# SmartSocket_v3.net
KiCad netlist of a schematic drawn in Altium Designer
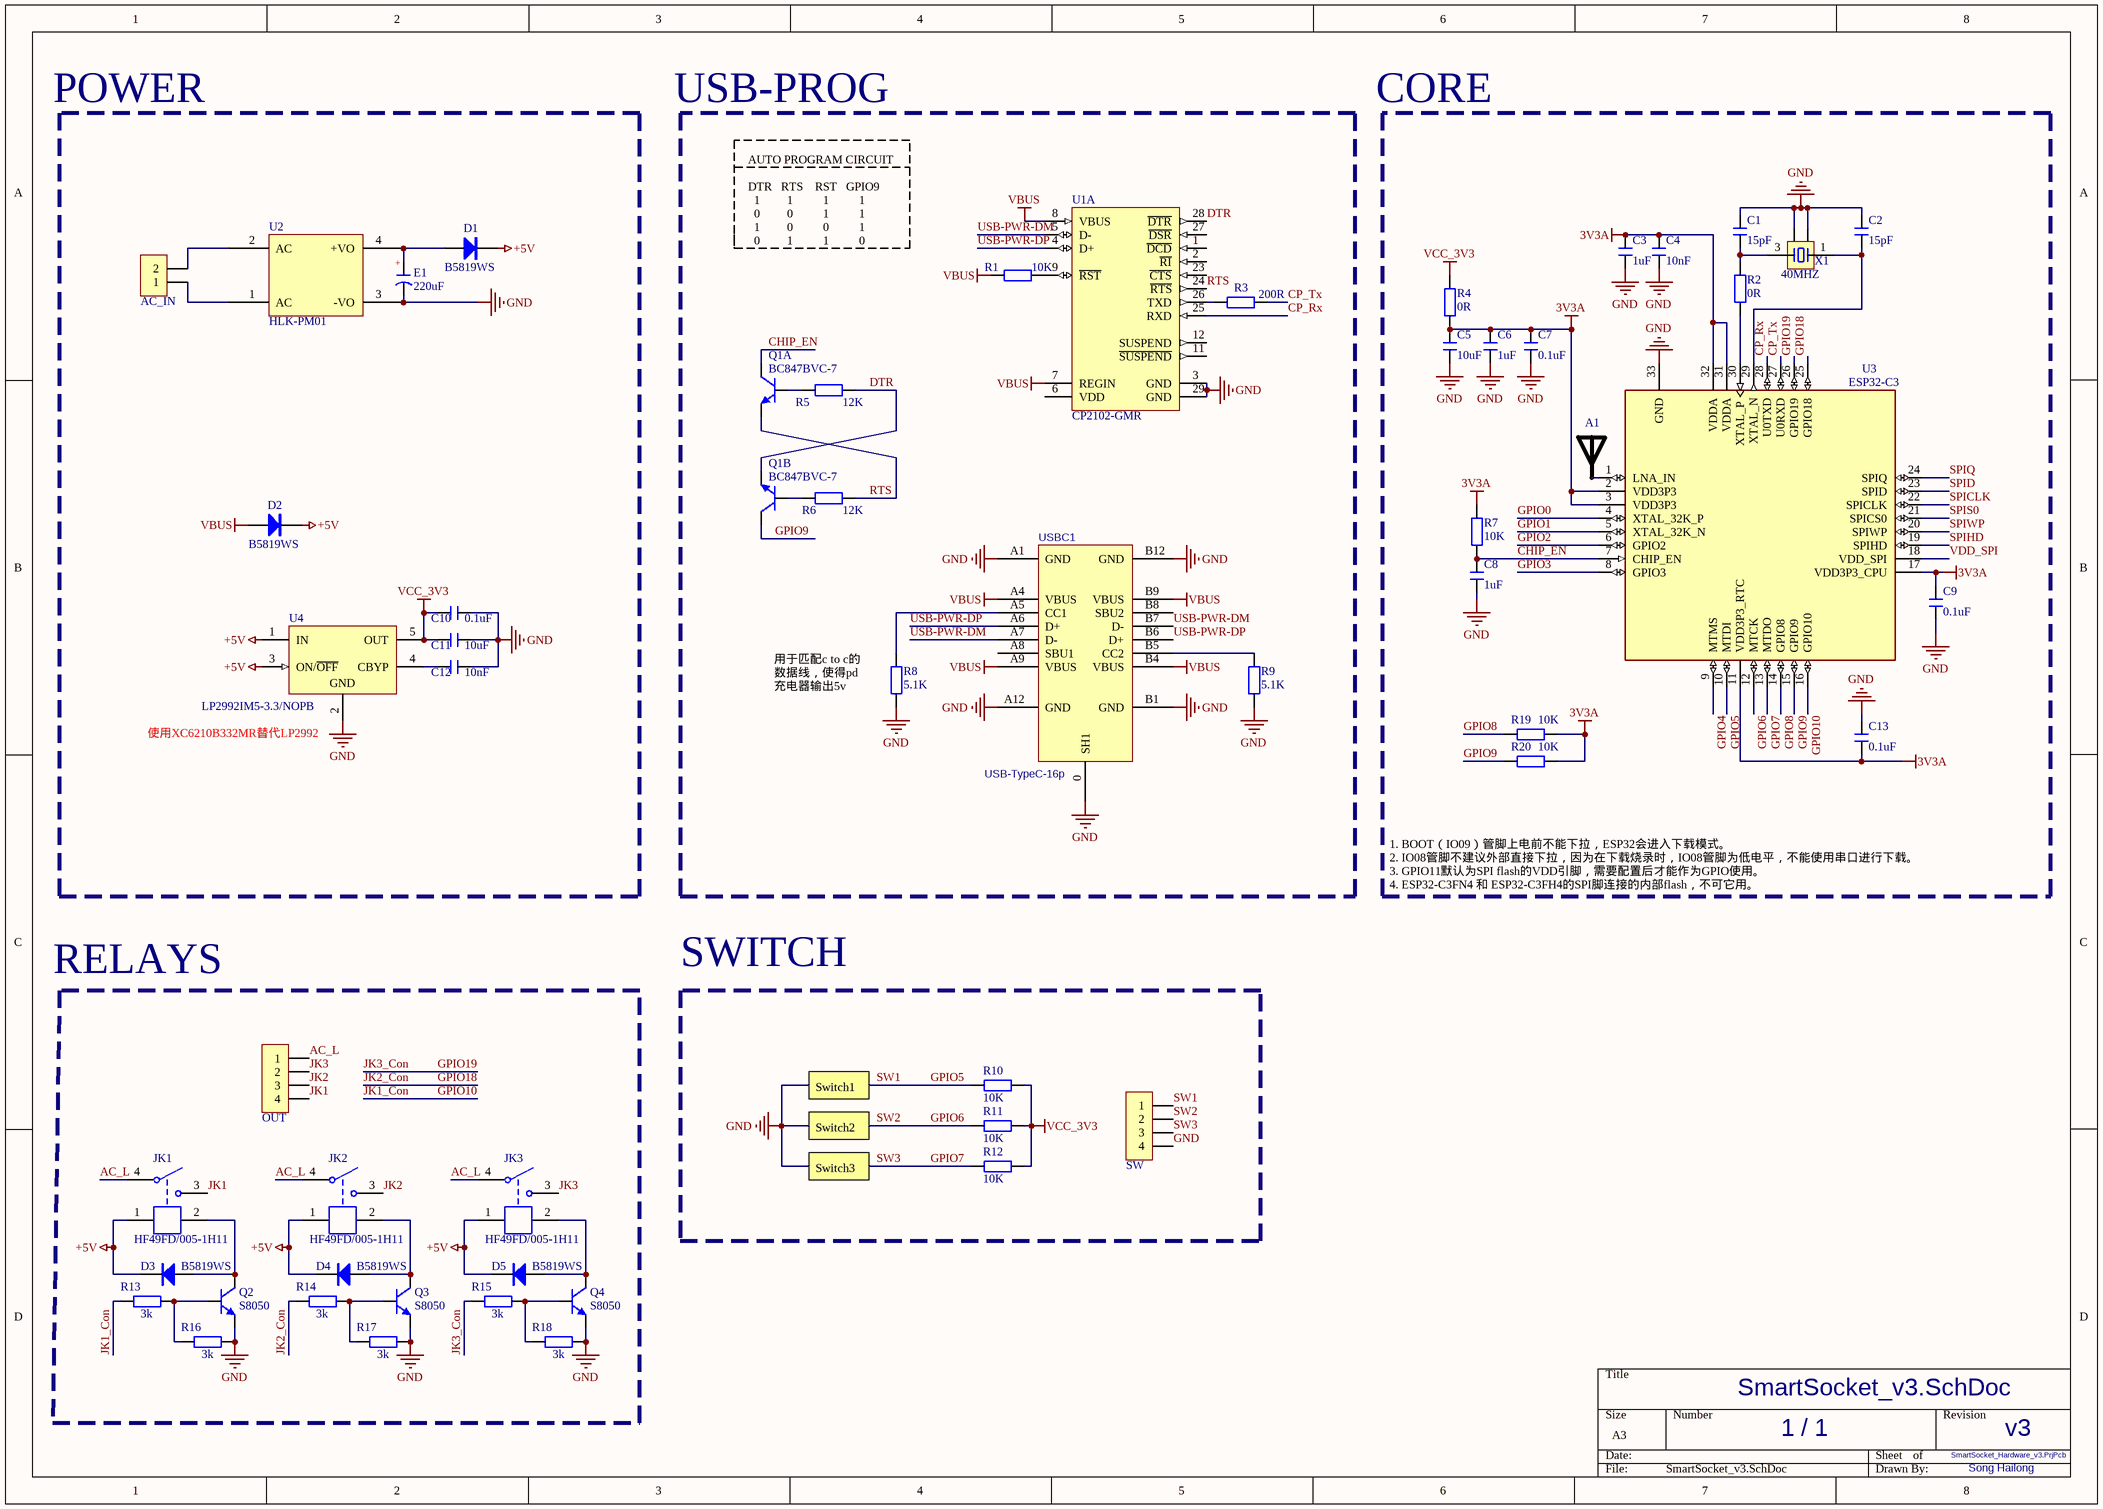
[diagram p0: SmartSocket_v3.SchDoc]

(export (version "E")
  (design (tool "Eeschema 10.0.6"))
  (components
    (comp (ref "A1")
      (value "AN2051-245")
      (footprint "AN2051-245")
      (description "天线AN2051-245")
      (libsource (lib "U8Library") (part "ANT-Rainsun-AP2051"))
    )
    (comp (ref "AC_IN")
      (value "HDR-1X2")
      (footprint "KF301-5.0-2P")
      (description "2P接插件")
      (fields (field (name "版权归属") "源创客"))
      (libsource (lib "U8Library") (part "Header 02 5.0"))
    )
    (comp (ref "C1")
      (value "15pF")
      (footprint "C 0402_L")
      (description "无极性贴片电容")
      (fields (field (name "版权归属") "源创客"))
      (libsource (lib "U8Library") (part "C"))
    )
    (comp (ref "C2")
      (value "15pF")
      (footprint "C 0402_L")
      (description "无极性贴片电容")
      (fields (field (name "版权归属") "源创客"))
      (libsource (lib "U8Library") (part "C"))
    )
    (comp (ref "C3")
      (value "1uF")
      (footprint "C 0402_L")
      (description "无极性贴片电容")
      (fields (field (name "版权归属") "源创客"))
      (libsource (lib "U8Library") (part "C"))
    )
    (comp (ref "C4")
      (value "10nF")
      (footprint "C 0402_L")
      (description "无极性贴片电容")
      (fields (field (name "版权归属") "源创客"))
      (libsource (lib "U8Library") (part "C"))
    )
    (comp (ref "C5")
      (value "10uF")
      (footprint "C 0402_L")
      (description "无极性贴片电容")
      (fields (field (name "版权归属") "源创客"))
      (libsource (lib "U8Library") (part "C"))
    )
    (comp (ref "C6")
      (value "1uF")
      (footprint "C 0402_L")
      (description "无极性贴片电容")
      (fields (field (name "版权归属") "源创客"))
      (libsource (lib "U8Library") (part "C"))
    )
    (comp (ref "C7")
      (value "0.1uF")
      (footprint "C 0402_L")
      (description "无极性贴片电容")
      (fields (field (name "版权归属") "源创客"))
      (libsource (lib "U8Library") (part "C"))
    )
    (comp (ref "C8")
      (value "1uF")
      (footprint "C 0402_L")
      (description "无极性贴片电容")
      (fields (field (name "版权归属") "源创客"))
      (libsource (lib "U8Library") (part "C"))
    )
    (comp (ref "C9")
      (value "0.1uF")
      (footprint "C 0402_L")
      (description "无极性贴片电容")
      (fields (field (name "版权归属") "源创客"))
      (libsource (lib "U8Library") (part "C"))
    )
    (comp (ref "C10")
      (value "0.1uF")
      (footprint "C 0402_L")
      (description "无极性贴片电容")
      (fields (field (name "版权归属") "源创客"))
      (libsource (lib "U8Library") (part "C"))
    )
    (comp (ref "C11")
      (value "10uF")
      (footprint "C 0402_L")
      (description "无极性贴片电容")
      (fields (field (name "版权归属") "源创客"))
      (libsource (lib "U8Library") (part "C"))
    )
    (comp (ref "C12")
      (value "10nF")
      (footprint "C 0402_L")
      (description "无极性贴片电容")
      (fields (field (name "版权归属") "源创客"))
      (libsource (lib "U8Library") (part "C"))
    )
    (comp (ref "C13")
      (value "0.1uF")
      (footprint "C 0402_L")
      (description "无极性贴片电容")
      (fields (field (name "版权归属") "源创客"))
      (libsource (lib "U8Library") (part "C"))
    )
    (comp (ref "D1")
      (value "B5819WS")
      (footprint "SOD-323")
      (description "肖特基二极管")
      (fields (field (name "版权归属") "源创客"))
      (libsource (lib "U8Library") (part "1N5819"))
    )
    (comp (ref "D2")
      (value "B5819WS")
      (footprint "SOD-323")
      (description "肖特基二极管")
      (fields (field (name "版权归属") "源创客"))
      (libsource (lib "U8Library") (part "1N5819"))
    )
    (comp (ref "D3")
      (value "B5819WS")
      (footprint "SOD-323")
      (description "肖特基二极管")
      (fields (field (name "版权归属") "源创客"))
      (libsource (lib "U8Library") (part "1N5819"))
    )
    (comp (ref "D4")
      (value "B5819WS")
      (footprint "SOD-323")
      (description "肖特基二极管")
      (fields (field (name "版权归属") "源创客"))
      (libsource (lib "U8Library") (part "1N5819"))
    )
    (comp (ref "D5")
      (value "B5819WS")
      (footprint "SOD-323")
      (description "肖特基二极管")
      (fields (field (name "版权归属") "源创客"))
      (libsource (lib "U8Library") (part "1N5819"))
    )
    (comp (ref "E1")
      (value "220uF")
      (footprint "CD D(7343)")
      (description "贴片钽电容")
      (fields (field (name "版权归属") "源创客"))
      (libsource (lib "U8Library") (part "C-CD"))
    )
    (comp (ref "JK1")
      (value "HF49FD/005-1H11")
      (footprint "HF49-XX-1H11")
      (description "5V一组常开")
      (libsource (lib "U8Library") (part "HF49FD/005-1H11"))
    )
    (comp (ref "JK2")
      (value "HF49FD/005-1H11")
      (footprint "HF49-XX-1H11")
      (description "5V一组常开")
      (libsource (lib "U8Library") (part "HF49FD/005-1H11"))
    )
    (comp (ref "JK3")
      (value "HF49FD/005-1H11")
      (footprint "HF49-XX-1H11")
      (description "5V一组常开")
      (libsource (lib "U8Library") (part "HF49FD/005-1H11"))
    )
    (comp (ref "OUT")
      (value "HDR-1X4")
      (footprint "KF301-5.0-4P")
      (description "4P接插件")
      (fields (field (name "版权归属") "源创客"))
      (libsource (lib "U8Library") (part "Header 04 5.0"))
    )
    (comp (ref "Q1")
      (value "BC847BVC-7")
      (footprint "SOT563-6")
      (libsource (lib "U8Library") (part "BC847BVC-7"))
    )
    (comp (ref "Q2")
      (value "S8050")
      (footprint "SOT23-3N")
      (description "高频放大-NPN型")
      (fields (field (name "版权归属") "源创客"))
      (libsource (lib "U8Library") (part "8050-SMD"))
    )
    (comp (ref "Q3")
      (value "S8050")
      (footprint "SOT23-3N")
      (description "高频放大-NPN型")
      (fields (field (name "版权归属") "源创客"))
      (libsource (lib "U8Library") (part "8050-SMD"))
    )
    (comp (ref "Q4")
      (value "S8050")
      (footprint "SOT23-3N")
      (description "高频放大-NPN型")
      (fields (field (name "版权归属") "源创客"))
      (libsource (lib "U8Library") (part "8050-SMD"))
    )
    (comp (ref "R1")
      (value "10K")
      (footprint "R 0402_L")
      (description "贴片电阻")
      (fields (field (name "版权归属") "源创客"))
      (libsource (lib "U8Library") (part "R"))
    )
    (comp (ref "R2")
      (value "0R")
      (footprint "R 0402_L")
      (description "贴片电阻")
      (fields (field (name "版权归属") "源创客"))
      (libsource (lib "U8Library") (part "R"))
    )
    (comp (ref "R3")
      (value "200R")
      (footprint "R 0402_L")
      (description "贴片电阻")
      (fields (field (name "版权归属") "源创客"))
      (libsource (lib "U8Library") (part "R"))
    )
    (comp (ref "R4")
      (value "0R")
      (footprint "R 0402_L")
      (description "贴片电阻")
      (fields (field (name "版权归属") "源创客"))
      (libsource (lib "U8Library") (part "R"))
    )
    (comp (ref "R5")
      (value "12K")
      (footprint "R 0402_L")
      (description "贴片电阻")
      (fields (field (name "版权归属") "源创客"))
      (libsource (lib "U8Library") (part "R"))
    )
    (comp (ref "R6")
      (value "12K")
      (footprint "R 0402_L")
      (description "贴片电阻")
      (fields (field (name "版权归属") "源创客"))
      (libsource (lib "U8Library") (part "R"))
    )
    (comp (ref "R7")
      (value "10K")
      (footprint "R 0402_L")
      (description "贴片电阻")
      (fields (field (name "版权归属") "源创客"))
      (libsource (lib "U8Library") (part "R"))
    )
    (comp (ref "R8")
      (value "5.1K")
      (footprint "R 0402_L")
      (description "贴片电阻")
      (fields (field (name "版权归属") "源创客"))
      (libsource (lib "U8Library") (part "R"))
    )
    (comp (ref "R9")
      (value "5.1K")
      (footprint "R 0402_L")
      (description "贴片电阻")
      (fields (field (name "版权归属") "源创客"))
      (libsource (lib "U8Library") (part "R"))
    )
    (comp (ref "R10")
      (value "10K")
      (footprint "R 0402_L")
      (description "贴片电阻")
      (fields (field (name "版权归属") "源创客"))
      (libsource (lib "U8Library") (part "R"))
    )
    (comp (ref "R11")
      (value "10K")
      (footprint "R 0402_L")
      (description "贴片电阻")
      (fields (field (name "版权归属") "源创客"))
      (libsource (lib "U8Library") (part "R"))
    )
    (comp (ref "R12")
      (value "10K")
      (footprint "R 0402_L")
      (description "贴片电阻")
      (fields (field (name "版权归属") "源创客"))
      (libsource (lib "U8Library") (part "R"))
    )
    (comp (ref "R13")
      (value "3k")
      (footprint "R 0402_L")
      (description "贴片电阻")
      (fields (field (name "版权归属") "源创客"))
      (libsource (lib "U8Library") (part "R"))
    )
    (comp (ref "R14")
      (value "3k")
      (footprint "R 0402_L")
      (description "贴片电阻")
      (fields (field (name "版权归属") "源创客"))
      (libsource (lib "U8Library") (part "R"))
    )
    (comp (ref "R15")
      (value "3k")
      (footprint "R 0402_L")
      (description "贴片电阻")
      (fields (field (name "版权归属") "源创客"))
      (libsource (lib "U8Library") (part "R"))
    )
    (comp (ref "R16")
      (value "3k")
      (footprint "R 0402_L")
      (description "贴片电阻")
      (fields (field (name "版权归属") "源创客"))
      (libsource (lib "U8Library") (part "R"))
    )
    (comp (ref "R17")
      (value "3k")
      (footprint "R 0402_L")
      (description "贴片电阻")
      (fields (field (name "版权归属") "源创客"))
      (libsource (lib "U8Library") (part "R"))
    )
    (comp (ref "R18")
      (value "3k")
      (footprint "R 0402_L")
      (description "贴片电阻")
      (fields (field (name "版权归属") "源创客"))
      (libsource (lib "U8Library") (part "R"))
    )
    (comp (ref "R19")
      (value "10K")
      (footprint "R 0402_L")
      (description "贴片电阻")
      (fields (field (name "版权归属") "源创客"))
      (libsource (lib "U8Library") (part "R"))
    )
    (comp (ref "R20")
      (value "10K")
      (footprint "R 0402_L")
      (description "贴片电阻")
      (fields (field (name "版权归属") "源创客"))
      (libsource (lib "U8Library") (part "R"))
    )
    (comp (ref "SW")
      (value "HDR-1X4")
      (footprint "HDR2.54-LI-4P")
      (description "4P接插件")
      (fields (field (name "版权归属") "源创客"))
      (libsource (lib "U8Library") (part "Header 04 2.54"))
    )
    (comp (ref "U1")
      (value "CP2102-GMR")
      (footprint "SLAB-QFN-28-3125x3125TP_M")
      (description "Single-Chip USB to URAT Bridge, 3.3 V, -40 to 85 degC, 28-Pin QFN, RoHS, Tape and Reel")
      (fields (field (name "MANUFACTURER") "Silicon Labs"))
      (libsource (lib "Altium Content Vault") (part "SLAB-CP210X-QFN-28-29"))
    )
    (comp (ref "U2")
      (value "HLK-PM01")
      (footprint "HLK-PM01")
      (description "220V转5V模块")
      (libsource (lib "ESP8266控制器") (part "Component_1"))
    )
    (comp (ref "U3")
      (value "ESP32-C3")
      (footprint "QFN32 5x5_M")
      (fields (field (name "MF") "Espressif Systems") (field (name "MP") "ESP32-C3FH4"))
      (libsource (lib "U8Library") (part "ESP32-C3"))
    )
    (comp (ref "U4")
      (value "LP2992IM5-3.3/NOPB")
      (footprint "DBV0005A_N")
      (description "Micropower 250 mA Low-Noise Ultra Low-Dropout Regulator, 5-pin SOT-23, Pb-Free")
      (fields (field (name "MANUFACTURER") "Texas Instruments"))
      (libsource (lib "Altium Content Vault") (part "PM-REG-LP2985-SOT5"))
    )
    (comp (ref "USBC1")
      (value "USB-TypeC-16p")
      (footprint "TYPE-C-USB-16P-1")
      (libsource (lib "15.1 - type-c-sch") (part "USB-TypeC-16p"))
    )
    (comp (ref "X1")
      (value "40MHZ")
      (footprint "OSC 3225-4P")
      (description "4脚无源晶振")
      (fields (field (name "版权归属") "源创客"))
      (libsource (lib "U8Library") (part "XTAL-4P"))
    )
  )
  (nets
    (net (code "1") (name "+5V") (class "Default")
      (node (ref "D1") (pin "2") (pinfunction "K_2") (pintype "passive"))
      (node (ref "D2") (pin "2") (pinfunction "K_2") (pintype "passive"))
      (node (ref "D3") (pin "2") (pinfunction "K_2") (pintype "passive"))
      (node (ref "D4") (pin "2") (pinfunction "K_2") (pintype "passive"))
      (node (ref "D5") (pin "2") (pinfunction "K_2") (pintype "passive"))
      (node (ref "JK1") (pin "1") (pinfunction "1_1") (pintype "passive"))
      (node (ref "JK2") (pin "1") (pinfunction "1_1") (pintype "passive"))
      (node (ref "JK3") (pin "1") (pinfunction "1_1") (pintype "passive"))
      (node (ref "U4") (pin "1") (pinfunction "IN_1") (pintype "power_in"))
      (node (ref "U4") (pin "3") (pinfunction "ON/~{OFF}_3") (pintype "input"))
    )
    (net (code "2") (name "/AC_L") (class "Default")
      (node (ref "JK1") (pin "4") (pinfunction "4_4") (pintype "passive"))
      (node (ref "JK2") (pin "4") (pinfunction "4_4") (pintype "passive"))
      (node (ref "JK3") (pin "4") (pinfunction "4_4") (pintype "passive"))
      (node (ref "OUT") (pin "1") (pinfunction "1_1") (pintype "passive"))
    )
    (net (code "3") (name "/CHIP_EN") (class "Default")
      (node (ref "C8") (pin "2") (pinfunction "2_2") (pintype "passive"))
      (node (ref "Q1") (pin "6") (pinfunction "C1_6") (pintype "passive"))
      (node (ref "R7") (pin "1") (pinfunction "1_1") (pintype "passive"))
      (node (ref "U3") (pin "7") (pinfunction "CHIP_EN_7") (pintype "input"))
    )
    (net (code "4") (name "/CP_Rx") (class "Default")
      (node (ref "U1") (pin "25") (pinfunction "RXD_25") (pintype "input"))
      (node (ref "U3") (pin "28") (pinfunction "U0TXD_28") (pintype "bidirectional"))
    )
    (net (code "5") (name "/CP_Tx") (class "Default")
      (node (ref "R3") (pin "2") (pinfunction "2_2") (pintype "passive"))
      (node (ref "U3") (pin "27") (pinfunction "U0RXD_27") (pintype "bidirectional"))
    )
    (net (code "6") (name "/DTR") (class "Default")
      (node (ref "Q1") (pin "4") (pinfunction "E2_4") (pintype "passive"))
      (node (ref "R5") (pin "2") (pinfunction "2_2") (pintype "passive"))
      (node (ref "U1") (pin "28") (pinfunction "~{DTR}_28") (pintype "output"))
    )
    (net (code "7") (name "/GPIO0") (class "Default")
      (node (ref "U3") (pin "4") (pinfunction "XTAL_32K_P_4") (pintype "bidirectional"))
    )
    (net (code "8") (name "/GPIO1") (class "Default")
      (node (ref "U3") (pin "5") (pinfunction "XTAL_32K_N_5") (pintype "bidirectional"))
    )
    (net (code "9") (name "/GPIO2") (class "Default")
      (node (ref "U3") (pin "6") (pinfunction "GPIO2_6") (pintype "bidirectional"))
    )
    (net (code "10") (name "/GPIO3") (class "Default")
      (node (ref "U3") (pin "8") (pinfunction "GPIO3_8") (pintype "bidirectional"))
    )
    (net (code "11") (name "/GPIO4") (class "Default")
      (node (ref "U3") (pin "9") (pinfunction "MTMS_9") (pintype "bidirectional"))
    )
    (net (code "12") (name "/GPIO5") (class "Default")
      (node (ref "R10") (pin "1") (pinfunction "1_1") (pintype "passive"))
      (node (ref "SW") (pin "1") (pinfunction "1_1") (pintype "passive"))
      (node (ref "U3") (pin "10") (pinfunction "MTDI_10") (pintype "bidirectional"))
    )
    (net (code "13") (name "/GPIO6") (class "Default")
      (node (ref "R11") (pin "1") (pinfunction "1_1") (pintype "passive"))
      (node (ref "SW") (pin "2") (pinfunction "2_2") (pintype "passive"))
      (node (ref "U3") (pin "12") (pinfunction "MTCK_12") (pintype "bidirectional"))
    )
    (net (code "14") (name "/GPIO7") (class "Default")
      (node (ref "R12") (pin "1") (pinfunction "1_1") (pintype "passive"))
      (node (ref "SW") (pin "3") (pinfunction "3_3") (pintype "passive"))
      (node (ref "U3") (pin "13") (pinfunction "MTDO_13") (pintype "bidirectional"))
    )
    (net (code "15") (name "/GPIO8") (class "Default")
      (node (ref "R19") (pin "2") (pinfunction "2_2") (pintype "passive"))
      (node (ref "U3") (pin "14") (pinfunction "GPIO8_14") (pintype "bidirectional"))
    )
    (net (code "16") (name "/GPIO9") (class "Default")
      (node (ref "Q1") (pin "3") (pinfunction "C2_3") (pintype "passive"))
      (node (ref "R20") (pin "2") (pinfunction "2_2") (pintype "passive"))
      (node (ref "U3") (pin "15") (pinfunction "GPIO9_15") (pintype "bidirectional"))
    )
    (net (code "17") (name "/GPIO10") (class "Default")
      (node (ref "R13") (pin "2") (pinfunction "2_2") (pintype "passive"))
      (node (ref "U3") (pin "16") (pinfunction "GPIO10_16") (pintype "bidirectional"))
    )
    (net (code "18") (name "/GPIO18") (class "Default")
      (node (ref "R14") (pin "2") (pinfunction "2_2") (pintype "passive"))
      (node (ref "U3") (pin "25") (pinfunction "GPIO18_25") (pintype "bidirectional"))
    )
    (net (code "19") (name "/GPIO19") (class "Default")
      (node (ref "R15") (pin "2") (pinfunction "2_2") (pintype "passive"))
      (node (ref "U3") (pin "26") (pinfunction "GPIO19_26") (pintype "bidirectional"))
    )
    (net (code "20") (name "/JK1") (class "Default")
      (node (ref "JK1") (pin "3") (pinfunction "3_3") (pintype "passive"))
      (node (ref "OUT") (pin "4") (pinfunction "4_4") (pintype "passive"))
    )
    (net (code "21") (name "/JK2") (class "Default")
      (node (ref "JK2") (pin "3") (pinfunction "3_3") (pintype "passive"))
      (node (ref "OUT") (pin "3") (pinfunction "3_3") (pintype "passive"))
    )
    (net (code "22") (name "/JK3") (class "Default")
      (node (ref "JK3") (pin "3") (pinfunction "3_3") (pintype "passive"))
      (node (ref "OUT") (pin "2") (pinfunction "2_2") (pintype "passive"))
    )
    (net (code "23") (name "/RTS") (class "Default")
      (node (ref "Q1") (pin "1") (pinfunction "E1_1") (pintype "passive"))
      (node (ref "R6") (pin "2") (pinfunction "2_2") (pintype "passive"))
      (node (ref "U1") (pin "24") (pinfunction "~{RTS}_24") (pintype "output"))
    )
    (net (code "24") (name "/SPICLK") (class "Default")
      (node (ref "U3") (pin "22") (pinfunction "SPICLK_22") (pintype "bidirectional"))
    )
    (net (code "25") (name "/SPID") (class "Default")
      (node (ref "U3") (pin "23") (pinfunction "SPID_23") (pintype "bidirectional"))
    )
    (net (code "26") (name "/SPIHD") (class "Default")
      (node (ref "U3") (pin "19") (pinfunction "SPIHD_19") (pintype "bidirectional"))
    )
    (net (code "27") (name "/SPIQ") (class "Default")
      (node (ref "U3") (pin "24") (pinfunction "SPIQ_24") (pintype "bidirectional"))
    )
    (net (code "28") (name "/SPIS0") (class "Default")
      (node (ref "U3") (pin "21") (pinfunction "SPICS0_21") (pintype "bidirectional"))
    )
    (net (code "29") (name "/SPIWP") (class "Default")
      (node (ref "U3") (pin "20") (pinfunction "SPIWP_20") (pintype "bidirectional"))
    )
    (net (code "30") (name "/USB-PWR-DM") (class "Default")
      (node (ref "U1") (pin "5") (pinfunction "D-_5") (pintype "bidirectional"))
      (node (ref "USBC1") (pin "A7") (pinfunction "D-_A7") (pintype "passive"))
      (node (ref "USBC1") (pin "B7") (pinfunction "D-_B7") (pintype "passive"))
    )
    (net (code "31") (name "/USB-PWR-DP") (class "Default")
      (node (ref "U1") (pin "4") (pinfunction "D+_4") (pintype "bidirectional"))
      (node (ref "USBC1") (pin "A6") (pinfunction "D+_A6") (pintype "passive"))
      (node (ref "USBC1") (pin "B6") (pinfunction "D+_B6") (pintype "passive"))
    )
    (net (code "32") (name "/VDD_SPI") (class "Default")
      (node (ref "U3") (pin "18") (pinfunction "VDD_SPI_18") (pintype "power_in"))
    )
    (net (code "33") (name "3V3A") (class "Default")
      (node (ref "C13") (pin "2") (pinfunction "2_2") (pintype "passive"))
      (node (ref "C3") (pin "2") (pinfunction "2_2") (pintype "passive"))
      (node (ref "C4") (pin "2") (pinfunction "2_2") (pintype "passive"))
      (node (ref "C5") (pin "2") (pinfunction "2_2") (pintype "passive"))
      (node (ref "C6") (pin "2") (pinfunction "2_2") (pintype "passive"))
      (node (ref "C7") (pin "2") (pinfunction "2_2") (pintype "passive"))
      (node (ref "C9") (pin "2") (pinfunction "2_2") (pintype "passive"))
      (node (ref "R19") (pin "1") (pinfunction "1_1") (pintype "passive"))
      (node (ref "R20") (pin "1") (pinfunction "1_1") (pintype "passive"))
      (node (ref "R4") (pin "1") (pinfunction "1_1") (pintype "passive"))
      (node (ref "R7") (pin "2") (pinfunction "2_2") (pintype "passive"))
      (node (ref "U3") (pin "11") (pinfunction "VDD3P3_RTC_11") (pintype "power_in"))
      (node (ref "U3") (pin "17") (pinfunction "VDD3P3_CPU_17") (pintype "power_in"))
      (node (ref "U3") (pin "2") (pinfunction "VDD3P3_2") (pintype "power_in"))
      (node (ref "U3") (pin "3") (pinfunction "VDD3P3_3") (pintype "power_in"))
      (node (ref "U3") (pin "31") (pinfunction "VDDA_31") (pintype "power_in"))
      (node (ref "U3") (pin "32") (pinfunction "VDDA_32") (pintype "power_in"))
    )
    (net (code "34") (name "GND") (class "Default")
      (node (ref "C1") (pin "2") (pinfunction "2_2") (pintype "passive"))
      (node (ref "C10") (pin "2") (pinfunction "2_2") (pintype "passive"))
      (node (ref "C11") (pin "2") (pinfunction "2_2") (pintype "passive"))
      (node (ref "C12") (pin "2") (pinfunction "2_2") (pintype "passive"))
      (node (ref "C13") (pin "1") (pinfunction "1_1") (pintype "passive"))
      (node (ref "C2") (pin "2") (pinfunction "2_2") (pintype "passive"))
      (node (ref "C3") (pin "1") (pinfunction "1_1") (pintype "passive"))
      (node (ref "C4") (pin "1") (pinfunction "1_1") (pintype "passive"))
      (node (ref "C5") (pin "1") (pinfunction "1_1") (pintype "passive"))
      (node (ref "C6") (pin "1") (pinfunction "1_1") (pintype "passive"))
      (node (ref "C7") (pin "1") (pinfunction "1_1") (pintype "passive"))
      (node (ref "C8") (pin "1") (pinfunction "1_1") (pintype "passive"))
      (node (ref "C9") (pin "1") (pinfunction "1_1") (pintype "passive"))
      (node (ref "E1") (pin "2") (pinfunction "K_2") (pintype "passive"))
      (node (ref "Q2") (pin "2") (pinfunction "E_2") (pintype "passive"))
      (node (ref "Q3") (pin "2") (pinfunction "E_2") (pintype "passive"))
      (node (ref "Q4") (pin "2") (pinfunction "E_2") (pintype "passive"))
      (node (ref "R16") (pin "1") (pinfunction "1_1") (pintype "passive"))
      (node (ref "R17") (pin "1") (pinfunction "1_1") (pintype "passive"))
      (node (ref "R18") (pin "1") (pinfunction "1_1") (pintype "passive"))
      (node (ref "R8") (pin "1") (pinfunction "1_1") (pintype "passive"))
      (node (ref "R9") (pin "1") (pinfunction "1_1") (pintype "passive"))
      (node (ref "SW") (pin "4") (pinfunction "4_4") (pintype "passive"))
      (node (ref "U1") (pin "29") (pinfunction "GND_29") (pintype "power_in"))
      (node (ref "U1") (pin "3") (pinfunction "GND_3") (pintype "power_in"))
      (node (ref "U2") (pin "3") (pinfunction "-VO_3") (pintype "passive"))
      (node (ref "U3") (pin "33") (pinfunction "GND_33") (pintype "power_in"))
      (node (ref "U4") (pin "2") (pinfunction "GND_2") (pintype "power_in"))
      (node (ref "USBC1") (pin "0") (pinfunction "SH1_0") (pintype "passive"))
      (node (ref "USBC1") (pin "A1") (pinfunction "GND_A1") (pintype "passive"))
      (node (ref "USBC1") (pin "A12") (pinfunction "GND_A12") (pintype "passive"))
      (node (ref "USBC1") (pin "B1") (pinfunction "GND_B1") (pintype "passive"))
      (node (ref "USBC1") (pin "B12") (pinfunction "GND_B12") (pintype "passive"))
      (node (ref "X1") (pin "2") (pinfunction "2_2") (pintype "passive"))
      (node (ref "X1") (pin "4") (pinfunction "4_4") (pintype "passive"))
    )
    (net (code "35") (name "Net-(AC_IN-Pad1)") (class "Default")
      (node (ref "AC_IN") (pin "1") (pinfunction "1_1") (pintype "passive"))
      (node (ref "U2") (pin "1") (pinfunction "AC_1") (pintype "passive"))
    )
    (net (code "36") (name "Net-(AC_IN-Pad2)") (class "Default")
      (node (ref "AC_IN") (pin "2") (pinfunction "2_2") (pintype "passive"))
      (node (ref "U2") (pin "2") (pinfunction "AC_2") (pintype "passive"))
    )
    (net (code "37") (name "Net-(C1-Pad1)") (class "Default")
      (node (ref "C1") (pin "1") (pinfunction "1_1") (pintype "passive"))
      (node (ref "R2") (pin "2") (pinfunction "2_2") (pintype "passive"))
      (node (ref "X1") (pin "3") (pinfunction "3_3") (pintype "passive"))
    )
    (net (code "38") (name "Net-(D1-A)") (class "Default")
      (node (ref "D1") (pin "1") (pinfunction "A_1") (pintype "passive"))
      (node (ref "E1") (pin "1") (pinfunction "A_1") (pintype "passive"))
      (node (ref "U2") (pin "4") (pinfunction "+VO_4") (pintype "passive"))
    )
    (net (code "39") (name "Net-(D3-A)") (class "Default")
      (node (ref "D3") (pin "1") (pinfunction "A_1") (pintype "passive"))
      (node (ref "JK1") (pin "2") (pinfunction "2_2") (pintype "passive"))
      (node (ref "Q2") (pin "3") (pinfunction "C_3") (pintype "passive"))
    )
    (net (code "40") (name "Net-(D4-A)") (class "Default")
      (node (ref "D4") (pin "1") (pinfunction "A_1") (pintype "passive"))
      (node (ref "JK2") (pin "2") (pinfunction "2_2") (pintype "passive"))
      (node (ref "Q3") (pin "3") (pinfunction "C_3") (pintype "passive"))
    )
    (net (code "41") (name "Net-(D5-A)") (class "Default")
      (node (ref "D5") (pin "1") (pinfunction "A_1") (pintype "passive"))
      (node (ref "JK3") (pin "2") (pinfunction "2_2") (pintype "passive"))
      (node (ref "Q4") (pin "3") (pinfunction "C_3") (pintype "passive"))
    )
    (net (code "42") (name "Net-(Q1A-B1)") (class "Default")
      (node (ref "Q1") (pin "2") (pinfunction "B1_2") (pintype "passive"))
      (node (ref "R5") (pin "1") (pinfunction "1_1") (pintype "passive"))
    )
    (net (code "43") (name "Net-(Q1B-B2)") (class "Default")
      (node (ref "Q1") (pin "5") (pinfunction "B2_5") (pintype "passive"))
      (node (ref "R6") (pin "1") (pinfunction "1_1") (pintype "passive"))
    )
    (net (code "44") (name "Net-(Q2-B)") (class "Default")
      (node (ref "Q2") (pin "1") (pinfunction "B_1") (pintype "passive"))
      (node (ref "R13") (pin "1") (pinfunction "1_1") (pintype "passive"))
      (node (ref "R16") (pin "2") (pinfunction "2_2") (pintype "passive"))
    )
    (net (code "45") (name "Net-(Q3-B)") (class "Default")
      (node (ref "Q3") (pin "1") (pinfunction "B_1") (pintype "passive"))
      (node (ref "R14") (pin "1") (pinfunction "1_1") (pintype "passive"))
      (node (ref "R17") (pin "2") (pinfunction "2_2") (pintype "passive"))
    )
    (net (code "46") (name "Net-(Q4-B)") (class "Default")
      (node (ref "Q4") (pin "1") (pinfunction "B_1") (pintype "passive"))
      (node (ref "R15") (pin "1") (pinfunction "1_1") (pintype "passive"))
      (node (ref "R18") (pin "2") (pinfunction "2_2") (pintype "passive"))
    )
    (net (code "47") (name "Net-(U1A-TXD)") (class "Default")
      (node (ref "R3") (pin "1") (pinfunction "1_1") (pintype "passive"))
      (node (ref "U1") (pin "26") (pinfunction "TXD_26") (pintype "output"))
    )
    (net (code "48") (name "Net-(U1A-~{RST})") (class "Default")
      (node (ref "R1") (pin "2") (pinfunction "2_2") (pintype "passive"))
      (node (ref "U1") (pin "9") (pinfunction "~{RST}_9") (pintype "bidirectional"))
    )
    (net (code "49") (name "Net-(U3-LNA_IN)") (class "Default")
      (node (ref "A1") (pin "1") (pinfunction "1_1") (pintype "passive"))
      (node (ref "U3") (pin "1") (pinfunction "LNA_IN_1") (pintype "bidirectional"))
    )
    (net (code "50") (name "Net-(U3-XTAL_N)") (class "Default")
      (node (ref "C2") (pin "1") (pinfunction "1_1") (pintype "passive"))
      (node (ref "U3") (pin "29") (pinfunction "XTAL_N_29") (pintype "output"))
      (node (ref "X1") (pin "1") (pinfunction "1_1") (pintype "passive"))
    )
    (net (code "51") (name "Net-(U3-XTAL_P)") (class "Default")
      (node (ref "R2") (pin "1") (pinfunction "1_1") (pintype "passive"))
      (node (ref "U3") (pin "30") (pinfunction "XTAL_P_30") (pintype "input"))
    )
    (net (code "52") (name "Net-(U4-CBYP)") (class "Default")
      (node (ref "C12") (pin "1") (pinfunction "1_1") (pintype "passive"))
      (node (ref "U4") (pin "4") (pinfunction "CBYP_4") (pintype "passive"))
    )
    (net (code "53") (name "Net-(USBC1-CC1)") (class "Default")
      (node (ref "R8") (pin "2") (pinfunction "2_2") (pintype "passive"))
      (node (ref "USBC1") (pin "A5") (pinfunction "CC1_A5") (pintype "passive"))
    )
    (net (code "54") (name "Net-(USBC1-CC2)") (class "Default")
      (node (ref "R9") (pin "2") (pinfunction "2_2") (pintype "passive"))
      (node (ref "USBC1") (pin "B5") (pinfunction "CC2_B5") (pintype "passive"))
    )
    (net (code "55") (name "VBUS") (class "Default")
      (node (ref "D2") (pin "1") (pinfunction "A_1") (pintype "passive"))
      (node (ref "R1") (pin "1") (pinfunction "1_1") (pintype "passive"))
      (node (ref "U1") (pin "7") (pinfunction "REGIN_7") (pintype "power_in"))
      (node (ref "U1") (pin "8") (pinfunction "VBUS_8") (pintype "input"))
      (node (ref "USBC1") (pin "A4") (pinfunction "VBUS_A4") (pintype "passive"))
      (node (ref "USBC1") (pin "A9") (pinfunction "VBUS_A9") (pintype "passive"))
      (node (ref "USBC1") (pin "B4") (pinfunction "VBUS_B4") (pintype "passive"))
      (node (ref "USBC1") (pin "B9") (pinfunction "VBUS_B9") (pintype "passive"))
    )
    (net (code "56") (name "VCC_3V3") (class "Default")
      (node (ref "C10") (pin "1") (pinfunction "1_1") (pintype "passive"))
      (node (ref "C11") (pin "1") (pinfunction "1_1") (pintype "passive"))
      (node (ref "R10") (pin "2") (pinfunction "2_2") (pintype "passive"))
      (node (ref "R11") (pin "2") (pinfunction "2_2") (pintype "passive"))
      (node (ref "R12") (pin "2") (pinfunction "2_2") (pintype "passive"))
      (node (ref "R4") (pin "2") (pinfunction "2_2") (pintype "passive"))
      (node (ref "U4") (pin "5") (pinfunction "OUT_5") (pintype "power_in"))
    )
    (net (code "57") (name "unconnected-(U1A-SUSPEND-Pad12)") (class "Default")
      (node (ref "U1") (pin "12") (pinfunction "SUSPEND_12") (pintype "output"))
    )
    (net (code "58") (name "unconnected-(U1A-VDD-Pad6)") (class "Default")
      (node (ref "U1") (pin "6") (pinfunction "VDD_6") (pintype "power_in"))
    )
    (net (code "59") (name "unconnected-(U1A-~{CTS}-Pad23)") (class "Default")
      (node (ref "U1") (pin "23") (pinfunction "~{CTS}_23") (pintype "input"))
    )
    (net (code "60") (name "unconnected-(U1A-~{DCD}-Pad1)") (class "Default")
      (node (ref "U1") (pin "1") (pinfunction "~{DCD}_1") (pintype "input"))
    )
    (net (code "61") (name "unconnected-(U1A-~{DSR}-Pad27)") (class "Default")
      (node (ref "U1") (pin "27") (pinfunction "~{DSR}_27") (pintype "input"))
    )
    (net (code "62") (name "unconnected-(U1A-~{RI}-Pad2)") (class "Default")
      (node (ref "U1") (pin "2") (pinfunction "~{RI}_2") (pintype "input"))
    )
    (net (code "63") (name "unconnected-(U1A-~{SUSPEND}-Pad11)") (class "Default")
      (node (ref "U1") (pin "11") (pinfunction "~{SUSPEND}_11") (pintype "output"))
    )
    (net (code "64") (name "unconnected-(USBC1-SBU1-PadA8)") (class "Default")
      (node (ref "USBC1") (pin "A8") (pinfunction "SBU1_A8") (pintype "passive"))
    )
    (net (code "65") (name "unconnected-(USBC1-SBU2-PadB8)") (class "Default")
      (node (ref "USBC1") (pin "B8") (pinfunction "SBU2_B8") (pintype "passive"))
    )
  )
)
